# led.net
KiCad netlist of a schematic drawn in Altium Designer
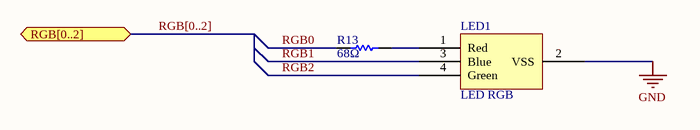
[diagram p0: led.SchDoc]

(export (version "E")
  (design (tool "Eeschema 10.0.6"))
  (components
    (comp (ref "LED1")
      (value "LED RGB")
      (footprint "Led RGB")
      (libsource (lib "libProject") (part "LED RGB"))
    )
    (comp (ref "R13")
      (value "68Ω")
      (footprint "RESISTANCE")
      (description "Resistor")
      (fields (field (name "Comment") "Res1") (field (name "PUBLISHER") "Altium Limited"))
      (libsource (lib "Miscellaneous Devices") (part "Res1"))
    )
  )
  (nets
    (net (code "1") (name "/RGB0") (class "Default")
      (node (ref "R13") (pin "1") (pinfunction "1_1") (pintype "passive"))
    )
    (net (code "2") (name "/RGB1") (class "Default")
      (node (ref "LED1") (pin "3") (pinfunction "Blue_3") (pintype "passive"))
    )
    (net (code "3") (name "/RGB2") (class "Default")
      (node (ref "LED1") (pin "4") (pinfunction "Green_4") (pintype "passive"))
    )
    (net (code "5") (name "GND") (class "Default")
      (node (ref "LED1") (pin "2") (pinfunction "VSS_2") (pintype "power_in"))
    )
    (net (code "6") (name "Net-(LED1-Red)") (class "Default")
      (node (ref "LED1") (pin "1") (pinfunction "Red_1") (pintype "passive"))
      (node (ref "R13") (pin "2") (pinfunction "2_2") (pintype "passive"))
    )
  )
)
